# SIX_OUTPORT.net
KiCad netlist of a schematic drawn in Altium Designer
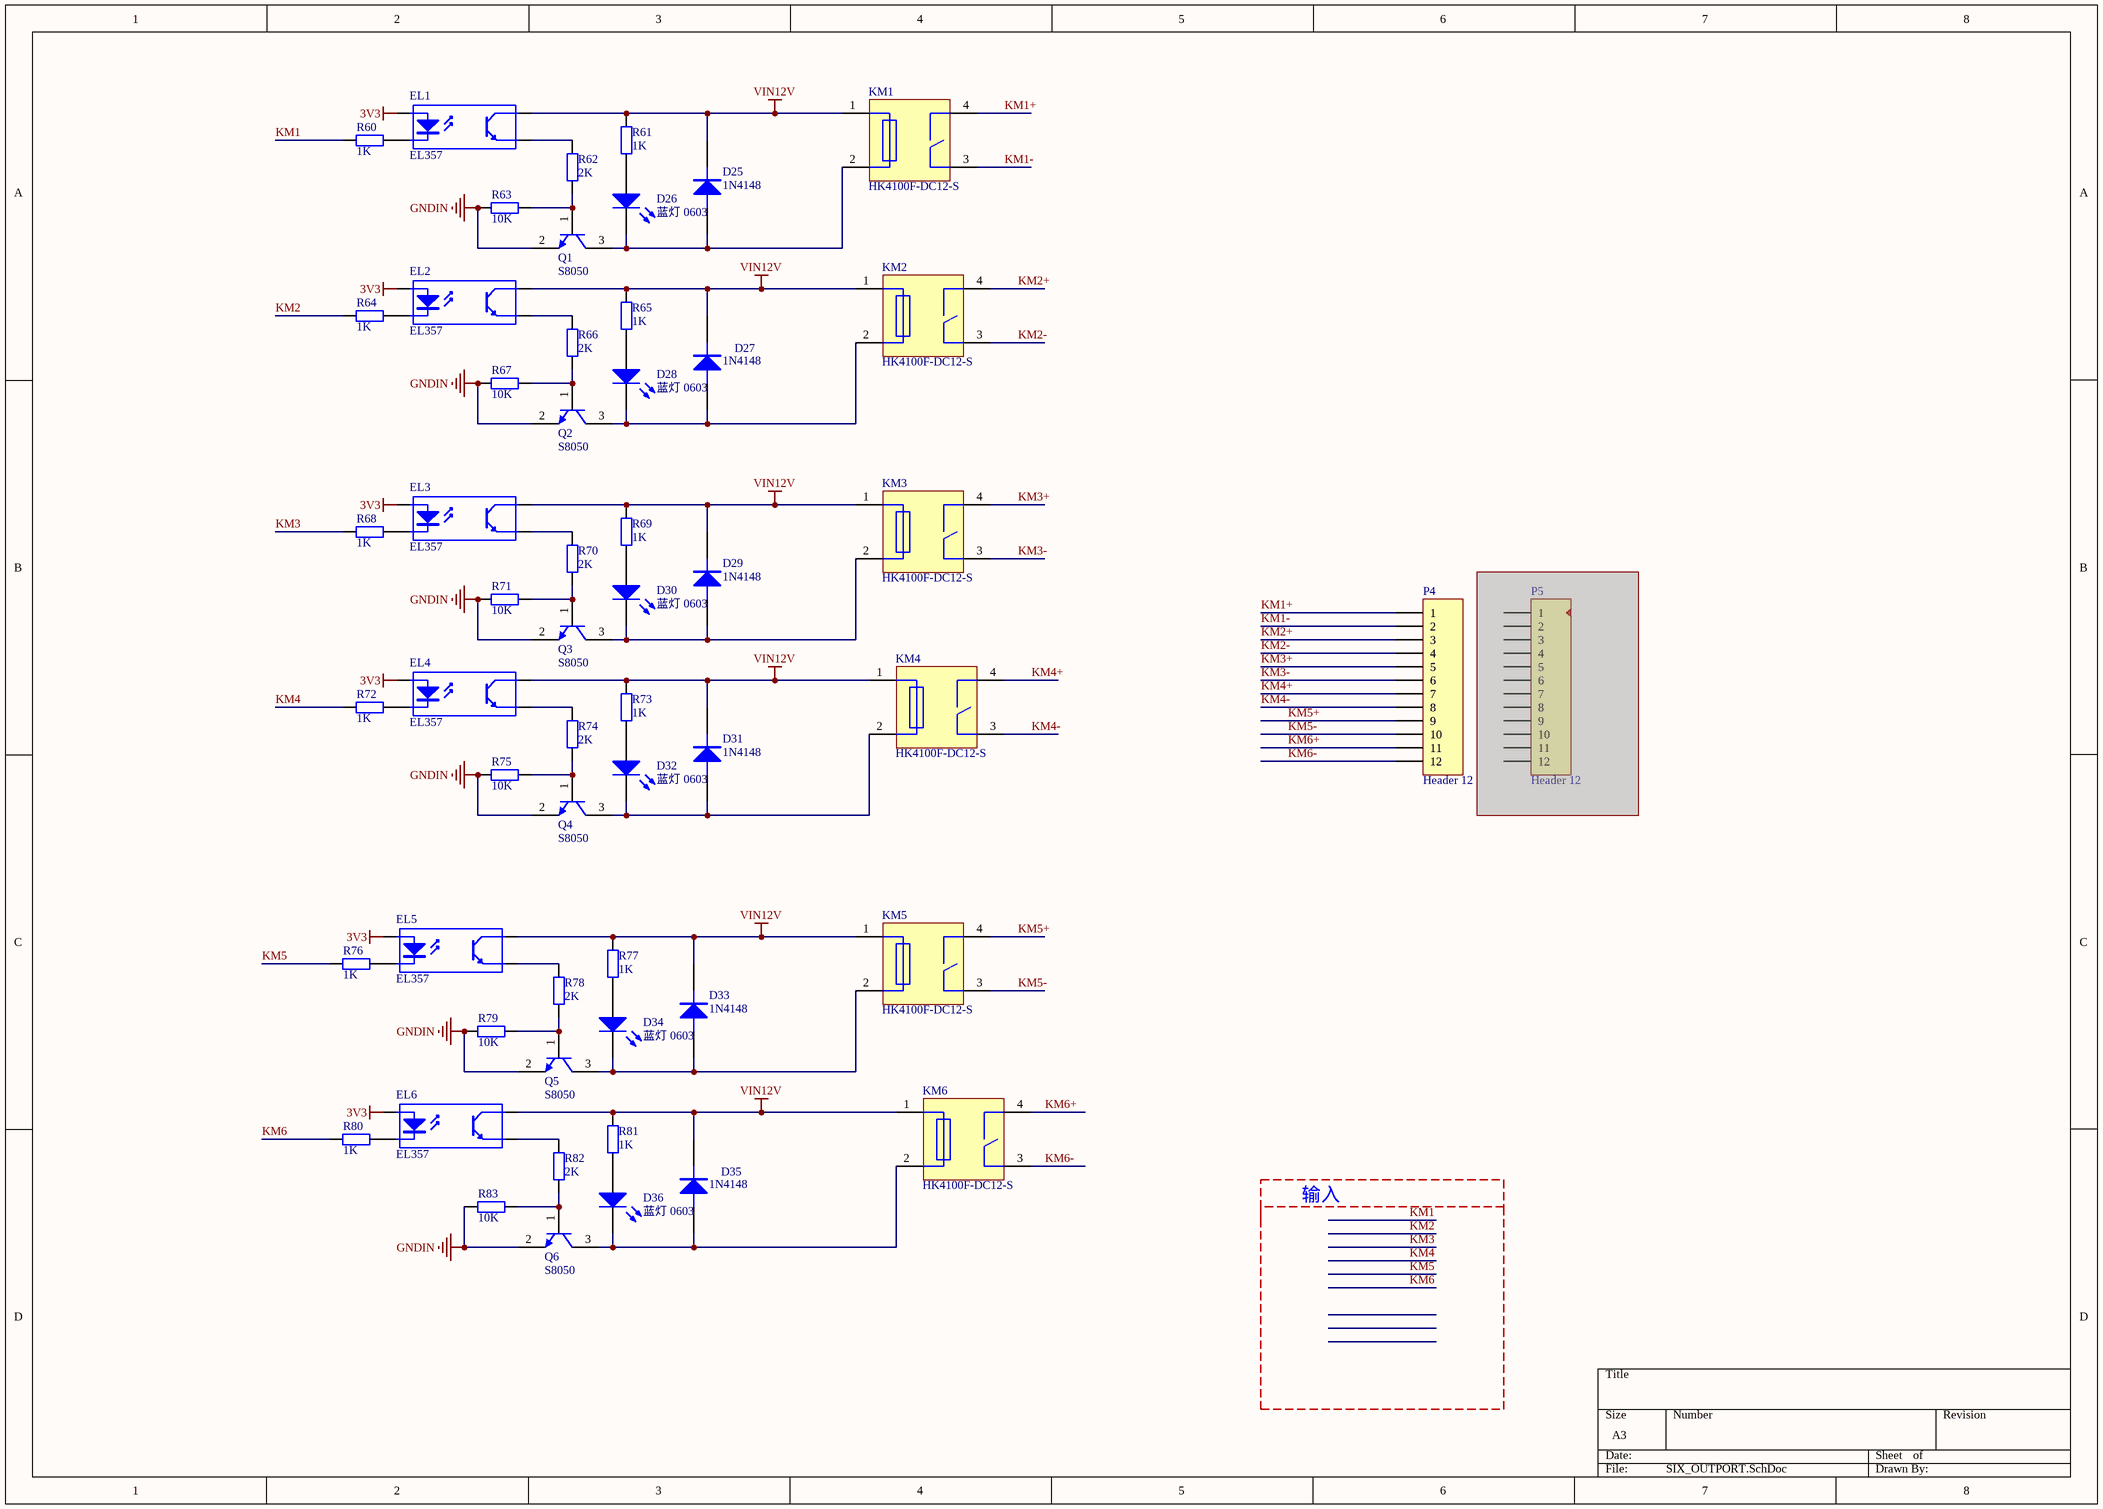
[diagram p0: SIX_OUTPORT.SchDoc]

(export (version "E")
  (design (tool "Eeschema 10.0.6"))
  (components
    (comp (ref "D25")
      (value "1N4148")
      (footprint "LC-LL-34")
      (description "Diode")
      (libsource (lib "Miscellaneous Devices") (part "DIODE"))
    )
    (comp (ref "D26")
      (value "蓝灯 0603")
      (footprint "LC-0603_LED_S1")
      (description "发光二极管")
      (libsource (lib "Miscellaneous Devices LC") (part "0603 蓝灯"))
    )
    (comp (ref "D27")
      (value "1N4148")
      (footprint "LC-LL-34")
      (description "Diode")
      (libsource (lib "Miscellaneous Devices") (part "DIODE"))
    )
    (comp (ref "D28")
      (value "蓝灯 0603")
      (footprint "LC-0603_LED_S1")
      (description "发光二极管")
      (libsource (lib "Miscellaneous Devices LC") (part "0603 蓝灯"))
    )
    (comp (ref "D29")
      (value "1N4148")
      (footprint "LC-LL-34")
      (description "Diode")
      (libsource (lib "Miscellaneous Devices") (part "DIODE"))
    )
    (comp (ref "D30")
      (value "蓝灯 0603")
      (footprint "LC-0603_LED_S1")
      (description "发光二极管")
      (libsource (lib "Miscellaneous Devices LC") (part "0603 蓝灯"))
    )
    (comp (ref "D31")
      (value "1N4148")
      (footprint "LC-LL-34")
      (description "Diode")
      (libsource (lib "Miscellaneous Devices") (part "DIODE"))
    )
    (comp (ref "D32")
      (value "蓝灯 0603")
      (footprint "LC-0603_LED_S1")
      (description "发光二极管")
      (libsource (lib "Miscellaneous Devices LC") (part "0603 蓝灯"))
    )
    (comp (ref "D33")
      (value "1N4148")
      (footprint "LC-LL-34")
      (description "Diode")
      (libsource (lib "Miscellaneous Devices") (part "DIODE"))
    )
    (comp (ref "D34")
      (value "蓝灯 0603")
      (footprint "LC-0603_LED_S1")
      (description "发光二极管")
      (libsource (lib "Miscellaneous Devices LC") (part "0603 蓝灯"))
    )
    (comp (ref "D35")
      (value "1N4148")
      (footprint "LC-LL-34")
      (description "Diode")
      (libsource (lib "Miscellaneous Devices") (part "DIODE"))
    )
    (comp (ref "D36")
      (value "蓝灯 0603")
      (footprint "LC-0603_LED_S1")
      (description "发光二极管")
      (libsource (lib "Miscellaneous Devices LC") (part "0603 蓝灯"))
    )
    (comp (ref "EL1")
      (value "EL357")
      (footprint "lc-sop-4_P2.54")
      (description "反射式光电传感器")
      (fields (field (name "PUBLISHER") "Altium Limited"))
      (libsource (lib "SCH_Footp1_Lian") (part "ST188"))
    )
    (comp (ref "EL2")
      (value "EL357")
      (footprint "lc-sop-4_P2.54")
      (description "反射式光电传感器")
      (fields (field (name "PUBLISHER") "Altium Limited"))
      (libsource (lib "SCH_Footp1_Lian") (part "ST188"))
    )
    (comp (ref "EL3")
      (value "EL357")
      (footprint "lc-sop-4_P2.54")
      (description "反射式光电传感器")
      (fields (field (name "PUBLISHER") "Altium Limited"))
      (libsource (lib "SCH_Footp1_Lian") (part "ST188"))
    )
    (comp (ref "EL4")
      (value "EL357")
      (footprint "lc-sop-4_P2.54")
      (description "反射式光电传感器")
      (fields (field (name "PUBLISHER") "Altium Limited"))
      (libsource (lib "SCH_Footp1_Lian") (part "ST188"))
    )
    (comp (ref "EL5")
      (value "EL357")
      (footprint "lc-sop-4_P2.54")
      (description "反射式光电传感器")
      (fields (field (name "PUBLISHER") "Altium Limited"))
      (libsource (lib "SCH_Footp1_Lian") (part "ST188"))
    )
    (comp (ref "EL6")
      (value "EL357")
      (footprint "lc-sop-4_P2.54")
      (description "反射式光电传感器")
      (fields (field (name "PUBLISHER") "Altium Limited"))
      (libsource (lib "SCH_Footp1_Lian") (part "ST188"))
    )
    (comp (ref "KM1")
      (value "HK4100F-DC12-S")
      (description "单刀双掷继电器")
      (libsource (lib "PCB_Project_2") (part "RELAY-HK4100F"))
    )
    (comp (ref "KM2")
      (value "HK4100F-DC12-S")
      (description "单刀双掷继电器")
      (libsource (lib "PCB_Project_2") (part "RELAY-HK4100F"))
    )
    (comp (ref "KM3")
      (value "HK4100F-DC12-S")
      (description "单刀双掷继电器")
      (libsource (lib "PCB_Project_2") (part "RELAY-HK4100F"))
    )
    (comp (ref "KM4")
      (value "HK4100F-DC12-S")
      (description "单刀双掷继电器")
      (libsource (lib "PCB_Project_2") (part "RELAY-HK4100F"))
    )
    (comp (ref "KM5")
      (value "HK4100F-DC12-S")
      (description "单刀双掷继电器")
      (libsource (lib "PCB_Project_2") (part "RELAY-HK4100F"))
    )
    (comp (ref "KM6")
      (value "HK4100F-DC12-S")
      (description "单刀双掷继电器")
      (libsource (lib "PCB_Project_2") (part "RELAY-HK4100F"))
    )
    (comp (ref "P4")
      (value "Header 12")
      (footprint "F5.08-12P")
      (description "Header, 12-Pin")
      (fields (field (name "PUBLISHER") "Altium Limited"))
      (libsource (lib "Miscellaneous Connectors") (part "Header 12"))
    )
    (comp (ref "P5")
      (value "Header 12")
      (footprint "F5.08-12P")
      (libsource (lib "HDR_fszhang") (part "Header 12"))
    )
    (comp (ref "Q1")
      (value "S8050")
      (footprint "LC-SOT-23(SOT-23-3)")
      (libsource (lib "SCH_Footp1_Lian") (part "S8050"))
    )
    (comp (ref "Q2")
      (value "S8050")
      (footprint "LC-SOT-23(SOT-23-3)")
      (libsource (lib "SCH_Footp1_Lian") (part "S8050"))
    )
    (comp (ref "Q3")
      (value "S8050")
      (footprint "LC-SOT-23(SOT-23-3)")
      (libsource (lib "SCH_Footp1_Lian") (part "S8050"))
    )
    (comp (ref "Q4")
      (value "S8050")
      (footprint "LC-SOT-23(SOT-23-3)")
      (libsource (lib "SCH_Footp1_Lian") (part "S8050"))
    )
    (comp (ref "Q5")
      (value "S8050")
      (footprint "LC-SOT-23(SOT-23-3)")
      (libsource (lib "SCH_Footp1_Lian") (part "S8050"))
    )
    (comp (ref "Q6")
      (value "S8050")
      (footprint "LC-SOT-23(SOT-23-3)")
      (libsource (lib "SCH_Footp1_Lian") (part "S8050"))
    )
    (comp (ref "R60")
      (value "1K")
      (footprint "LC-0603_R")
      (description "Resistor")
      (fields (field (name "PUBLISHER") "Altium Limited"))
      (libsource (lib "Miscellaneous Devices") (part "Res2"))
    )
    (comp (ref "R61")
      (value "1K")
      (footprint "LC-0603_R")
      (description "Resistor")
      (fields (field (name "PUBLISHER") "Altium Limited"))
      (libsource (lib "") (part "Res2_2"))
    )
    (comp (ref "R62")
      (value "2K")
      (footprint "LC-0603_R")
      (description "Resistor")
      (fields (field (name "PUBLISHER") "Altium Limited"))
      (libsource (lib "") (part "Res2_1"))
    )
    (comp (ref "R63")
      (value "10K")
      (footprint "LC-0603_R")
      (description "Resistor")
      (fields (field (name "PUBLISHER") "Altium Limited"))
      (libsource (lib "Miscellaneous Devices") (part "Res2"))
    )
    (comp (ref "R64")
      (value "1K")
      (footprint "LC-0603_R")
      (description "Resistor")
      (fields (field (name "PUBLISHER") "Altium Limited"))
      (libsource (lib "Miscellaneous Devices") (part "Res2"))
    )
    (comp (ref "R65")
      (value "1K")
      (footprint "LC-0603_R")
      (description "Resistor")
      (fields (field (name "PUBLISHER") "Altium Limited"))
      (libsource (lib "") (part "Res2_2"))
    )
    (comp (ref "R66")
      (value "2K")
      (footprint "LC-0603_R")
      (description "Resistor")
      (fields (field (name "PUBLISHER") "Altium Limited"))
      (libsource (lib "") (part "Res2_1"))
    )
    (comp (ref "R67")
      (value "10K")
      (footprint "LC-0603_R")
      (description "Resistor")
      (fields (field (name "PUBLISHER") "Altium Limited"))
      (libsource (lib "Miscellaneous Devices") (part "Res2"))
    )
    (comp (ref "R68")
      (value "1K")
      (footprint "LC-0603_R")
      (description "Resistor")
      (fields (field (name "PUBLISHER") "Altium Limited"))
      (libsource (lib "Miscellaneous Devices") (part "Res2"))
    )
    (comp (ref "R69")
      (value "1K")
      (footprint "LC-0603_R")
      (description "Resistor")
      (fields (field (name "PUBLISHER") "Altium Limited"))
      (libsource (lib "") (part "Res2_2"))
    )
    (comp (ref "R70")
      (value "2K")
      (footprint "LC-0603_R")
      (description "Resistor")
      (fields (field (name "PUBLISHER") "Altium Limited"))
      (libsource (lib "") (part "Res2_1"))
    )
    (comp (ref "R71")
      (value "10K")
      (footprint "LC-0603_R")
      (description "Resistor")
      (fields (field (name "PUBLISHER") "Altium Limited"))
      (libsource (lib "Miscellaneous Devices") (part "Res2"))
    )
    (comp (ref "R72")
      (value "1K")
      (footprint "LC-0603_R")
      (description "Resistor")
      (fields (field (name "PUBLISHER") "Altium Limited"))
      (libsource (lib "Miscellaneous Devices") (part "Res2"))
    )
    (comp (ref "R73")
      (value "1K")
      (footprint "LC-0603_R")
      (description "Resistor")
      (fields (field (name "PUBLISHER") "Altium Limited"))
      (libsource (lib "") (part "Res2_2"))
    )
    (comp (ref "R74")
      (value "2K")
      (footprint "LC-0603_R")
      (description "Resistor")
      (fields (field (name "PUBLISHER") "Altium Limited"))
      (libsource (lib "") (part "Res2_1"))
    )
    (comp (ref "R75")
      (value "10K")
      (footprint "LC-0603_R")
      (description "Resistor")
      (fields (field (name "PUBLISHER") "Altium Limited"))
      (libsource (lib "Miscellaneous Devices") (part "Res2"))
    )
    (comp (ref "R76")
      (value "1K")
      (footprint "LC-0603_R")
      (description "Resistor")
      (fields (field (name "PUBLISHER") "Altium Limited"))
      (libsource (lib "Miscellaneous Devices") (part "Res2"))
    )
    (comp (ref "R77")
      (value "1K")
      (footprint "LC-0603_R")
      (description "Resistor")
      (fields (field (name "PUBLISHER") "Altium Limited"))
      (libsource (lib "") (part "Res2_2"))
    )
    (comp (ref "R78")
      (value "2K")
      (footprint "LC-0603_R")
      (description "Resistor")
      (fields (field (name "PUBLISHER") "Altium Limited"))
      (libsource (lib "") (part "Res2_1"))
    )
    (comp (ref "R79")
      (value "10K")
      (footprint "LC-0603_R")
      (description "Resistor")
      (fields (field (name "PUBLISHER") "Altium Limited"))
      (libsource (lib "Miscellaneous Devices") (part "Res2"))
    )
    (comp (ref "R80")
      (value "1K")
      (footprint "LC-0603_R")
      (description "Resistor")
      (fields (field (name "PUBLISHER") "Altium Limited"))
      (libsource (lib "Miscellaneous Devices") (part "Res2"))
    )
    (comp (ref "R81")
      (value "1K")
      (footprint "LC-0603_R")
      (description "Resistor")
      (fields (field (name "PUBLISHER") "Altium Limited"))
      (libsource (lib "") (part "Res2_2"))
    )
    (comp (ref "R82")
      (value "2K")
      (footprint "LC-0603_R")
      (description "Resistor")
      (fields (field (name "PUBLISHER") "Altium Limited"))
      (libsource (lib "") (part "Res2_1"))
    )
    (comp (ref "R83")
      (value "10K")
      (footprint "LC-0603_R")
      (description "Resistor")
      (fields (field (name "PUBLISHER") "Altium Limited"))
      (libsource (lib "Miscellaneous Devices") (part "Res2"))
    )
  )
  (nets
    (net (code "1") (name "/KM1") (class "Default")
      (node (ref "R60") (pin "2") (pinfunction "2_2") (pintype "passive"))
    )
    (net (code "2") (name "/KM1+") (class "Default")
      (node (ref "KM1") (pin "4") (pinfunction "4_4") (pintype "passive"))
      (node (ref "P4") (pin "1") (pinfunction "1_1") (pintype "passive"))
    )
    (net (code "3") (name "/KM1-") (class "Default")
      (node (ref "KM1") (pin "3") (pinfunction "3_3") (pintype "passive"))
      (node (ref "P4") (pin "2") (pinfunction "2_2") (pintype "passive"))
    )
    (net (code "4") (name "/KM2") (class "Default")
      (node (ref "R64") (pin "2") (pinfunction "2_2") (pintype "passive"))
    )
    (net (code "5") (name "/KM2+") (class "Default")
      (node (ref "KM2") (pin "4") (pinfunction "4_4") (pintype "passive"))
      (node (ref "P4") (pin "3") (pinfunction "3_3") (pintype "passive"))
    )
    (net (code "6") (name "/KM2-") (class "Default")
      (node (ref "KM2") (pin "3") (pinfunction "3_3") (pintype "passive"))
      (node (ref "P4") (pin "4") (pinfunction "4_4") (pintype "passive"))
    )
    (net (code "7") (name "/KM3") (class "Default")
      (node (ref "R68") (pin "2") (pinfunction "2_2") (pintype "passive"))
    )
    (net (code "8") (name "/KM3+") (class "Default")
      (node (ref "KM3") (pin "4") (pinfunction "4_4") (pintype "passive"))
      (node (ref "P4") (pin "5") (pinfunction "5_5") (pintype "passive"))
    )
    (net (code "9") (name "/KM3-") (class "Default")
      (node (ref "KM3") (pin "3") (pinfunction "3_3") (pintype "passive"))
      (node (ref "P4") (pin "6") (pinfunction "6_6") (pintype "passive"))
    )
    (net (code "10") (name "/KM4") (class "Default")
      (node (ref "R72") (pin "2") (pinfunction "2_2") (pintype "passive"))
    )
    (net (code "11") (name "/KM4+") (class "Default")
      (node (ref "KM4") (pin "4") (pinfunction "4_4") (pintype "passive"))
      (node (ref "P4") (pin "7") (pinfunction "7_7") (pintype "passive"))
    )
    (net (code "12") (name "/KM4-") (class "Default")
      (node (ref "KM4") (pin "3") (pinfunction "3_3") (pintype "passive"))
      (node (ref "P4") (pin "8") (pinfunction "8_8") (pintype "passive"))
    )
    (net (code "13") (name "/KM5") (class "Default")
      (node (ref "R76") (pin "2") (pinfunction "2_2") (pintype "passive"))
    )
    (net (code "14") (name "/KM5+") (class "Default")
      (node (ref "KM5") (pin "4") (pinfunction "4_4") (pintype "passive"))
      (node (ref "P4") (pin "9") (pinfunction "9_9") (pintype "passive"))
    )
    (net (code "15") (name "/KM5-") (class "Default")
      (node (ref "KM5") (pin "3") (pinfunction "3_3") (pintype "passive"))
      (node (ref "P4") (pin "10") (pinfunction "10_10") (pintype "passive"))
    )
    (net (code "16") (name "/KM6") (class "Default")
      (node (ref "R80") (pin "2") (pinfunction "2_2") (pintype "passive"))
    )
    (net (code "17") (name "/KM6+") (class "Default")
      (node (ref "KM6") (pin "4") (pinfunction "4_4") (pintype "passive"))
      (node (ref "P4") (pin "11") (pinfunction "11_11") (pintype "passive"))
    )
    (net (code "18") (name "/KM6-") (class "Default")
      (node (ref "KM6") (pin "3") (pinfunction "3_3") (pintype "passive"))
      (node (ref "P4") (pin "12") (pinfunction "12_12") (pintype "passive"))
    )
    (net (code "19") (name "3V3") (class "Default")
      (node (ref "EL1") (pin "1") (pinfunction "A_1") (pintype "passive"))
      (node (ref "EL2") (pin "1") (pinfunction "A_1") (pintype "passive"))
      (node (ref "EL3") (pin "1") (pinfunction "A_1") (pintype "passive"))
      (node (ref "EL4") (pin "1") (pinfunction "A_1") (pintype "passive"))
      (node (ref "EL5") (pin "1") (pinfunction "A_1") (pintype "passive"))
      (node (ref "EL6") (pin "1") (pinfunction "A_1") (pintype "passive"))
    )
    (net (code "20") (name "GNDIN") (class "Default")
      (node (ref "Q1") (pin "2") (pinfunction "E_2") (pintype "passive"))
      (node (ref "Q2") (pin "2") (pinfunction "E_2") (pintype "passive"))
      (node (ref "Q3") (pin "2") (pinfunction "E_2") (pintype "passive"))
      (node (ref "Q4") (pin "2") (pinfunction "E_2") (pintype "passive"))
      (node (ref "Q5") (pin "2") (pinfunction "E_2") (pintype "passive"))
      (node (ref "Q6") (pin "2") (pinfunction "E_2") (pintype "passive"))
      (node (ref "R63") (pin "2") (pinfunction "2_2") (pintype "passive"))
      (node (ref "R67") (pin "2") (pinfunction "2_2") (pintype "passive"))
      (node (ref "R71") (pin "2") (pinfunction "2_2") (pintype "passive"))
      (node (ref "R75") (pin "2") (pinfunction "2_2") (pintype "passive"))
      (node (ref "R79") (pin "2") (pinfunction "2_2") (pintype "passive"))
      (node (ref "R83") (pin "2") (pinfunction "2_2") (pintype "passive"))
    )
    (net (code "21") (name "Net-(D25-A)") (class "Default")
      (node (ref "D25") (pin "1") (pinfunction "A_1") (pintype "passive"))
      (node (ref "D26") (pin "K") (pinfunction "K_K") (pintype "passive"))
      (node (ref "KM1") (pin "2") (pinfunction "2_2") (pintype "passive"))
      (node (ref "Q1") (pin "3") (pinfunction "C_3") (pintype "passive"))
    )
    (net (code "22") (name "Net-(D26-PadA)") (class "Default")
      (node (ref "D26") (pin "A") (pinfunction "A_A") (pintype "passive"))
      (node (ref "R61") (pin "2") (pinfunction "2_2") (pintype "passive"))
    )
    (net (code "23") (name "Net-(D27-A)") (class "Default")
      (node (ref "D27") (pin "1") (pinfunction "A_1") (pintype "passive"))
      (node (ref "D28") (pin "K") (pinfunction "K_K") (pintype "passive"))
      (node (ref "KM2") (pin "2") (pinfunction "2_2") (pintype "passive"))
      (node (ref "Q2") (pin "3") (pinfunction "C_3") (pintype "passive"))
    )
    (net (code "24") (name "Net-(D28-PadA)") (class "Default")
      (node (ref "D28") (pin "A") (pinfunction "A_A") (pintype "passive"))
      (node (ref "R65") (pin "2") (pinfunction "2_2") (pintype "passive"))
    )
    (net (code "25") (name "Net-(D29-A)") (class "Default")
      (node (ref "D29") (pin "1") (pinfunction "A_1") (pintype "passive"))
      (node (ref "D30") (pin "K") (pinfunction "K_K") (pintype "passive"))
      (node (ref "KM3") (pin "2") (pinfunction "2_2") (pintype "passive"))
      (node (ref "Q3") (pin "3") (pinfunction "C_3") (pintype "passive"))
    )
    (net (code "26") (name "Net-(D30-PadA)") (class "Default")
      (node (ref "D30") (pin "A") (pinfunction "A_A") (pintype "passive"))
      (node (ref "R69") (pin "2") (pinfunction "2_2") (pintype "passive"))
    )
    (net (code "27") (name "Net-(D31-A)") (class "Default")
      (node (ref "D31") (pin "1") (pinfunction "A_1") (pintype "passive"))
      (node (ref "D32") (pin "K") (pinfunction "K_K") (pintype "passive"))
      (node (ref "KM4") (pin "2") (pinfunction "2_2") (pintype "passive"))
      (node (ref "Q4") (pin "3") (pinfunction "C_3") (pintype "passive"))
    )
    (net (code "28") (name "Net-(D32-PadA)") (class "Default")
      (node (ref "D32") (pin "A") (pinfunction "A_A") (pintype "passive"))
      (node (ref "R73") (pin "2") (pinfunction "2_2") (pintype "passive"))
    )
    (net (code "29") (name "Net-(D33-A)") (class "Default")
      (node (ref "D33") (pin "1") (pinfunction "A_1") (pintype "passive"))
      (node (ref "D34") (pin "K") (pinfunction "K_K") (pintype "passive"))
      (node (ref "KM5") (pin "2") (pinfunction "2_2") (pintype "passive"))
      (node (ref "Q5") (pin "3") (pinfunction "C_3") (pintype "passive"))
    )
    (net (code "30") (name "Net-(D34-PadA)") (class "Default")
      (node (ref "D34") (pin "A") (pinfunction "A_A") (pintype "passive"))
      (node (ref "R77") (pin "2") (pinfunction "2_2") (pintype "passive"))
    )
    (net (code "31") (name "Net-(D35-A)") (class "Default")
      (node (ref "D35") (pin "1") (pinfunction "A_1") (pintype "passive"))
      (node (ref "D36") (pin "K") (pinfunction "K_K") (pintype "passive"))
      (node (ref "KM6") (pin "2") (pinfunction "2_2") (pintype "passive"))
      (node (ref "Q6") (pin "3") (pinfunction "C_3") (pintype "passive"))
    )
    (net (code "32") (name "Net-(D36-PadA)") (class "Default")
      (node (ref "D36") (pin "A") (pinfunction "A_A") (pintype "passive"))
      (node (ref "R81") (pin "2") (pinfunction "2_2") (pintype "passive"))
    )
    (net (code "33") (name "Net-(EL1-E)") (class "Default")
      (node (ref "EL1") (pin "3") (pinfunction "E_3") (pintype "passive"))
      (node (ref "R62") (pin "2") (pinfunction "2_2") (pintype "passive"))
    )
    (net (code "34") (name "Net-(EL1-K)") (class "Default")
      (node (ref "EL1") (pin "2") (pinfunction "K_2") (pintype "passive"))
      (node (ref "R60") (pin "1") (pinfunction "1_1") (pintype "passive"))
    )
    (net (code "35") (name "Net-(EL2-E)") (class "Default")
      (node (ref "EL2") (pin "3") (pinfunction "E_3") (pintype "passive"))
      (node (ref "R66") (pin "2") (pinfunction "2_2") (pintype "passive"))
    )
    (net (code "36") (name "Net-(EL2-K)") (class "Default")
      (node (ref "EL2") (pin "2") (pinfunction "K_2") (pintype "passive"))
      (node (ref "R64") (pin "1") (pinfunction "1_1") (pintype "passive"))
    )
    (net (code "37") (name "Net-(EL3-E)") (class "Default")
      (node (ref "EL3") (pin "3") (pinfunction "E_3") (pintype "passive"))
      (node (ref "R70") (pin "2") (pinfunction "2_2") (pintype "passive"))
    )
    (net (code "38") (name "Net-(EL3-K)") (class "Default")
      (node (ref "EL3") (pin "2") (pinfunction "K_2") (pintype "passive"))
      (node (ref "R68") (pin "1") (pinfunction "1_1") (pintype "passive"))
    )
    (net (code "39") (name "Net-(EL4-E)") (class "Default")
      (node (ref "EL4") (pin "3") (pinfunction "E_3") (pintype "passive"))
      (node (ref "R74") (pin "2") (pinfunction "2_2") (pintype "passive"))
    )
    (net (code "40") (name "Net-(EL4-K)") (class "Default")
      (node (ref "EL4") (pin "2") (pinfunction "K_2") (pintype "passive"))
      (node (ref "R72") (pin "1") (pinfunction "1_1") (pintype "passive"))
    )
    (net (code "41") (name "Net-(EL5-E)") (class "Default")
      (node (ref "EL5") (pin "3") (pinfunction "E_3") (pintype "passive"))
      (node (ref "R78") (pin "2") (pinfunction "2_2") (pintype "passive"))
    )
    (net (code "42") (name "Net-(EL5-K)") (class "Default")
      (node (ref "EL5") (pin "2") (pinfunction "K_2") (pintype "passive"))
      (node (ref "R76") (pin "1") (pinfunction "1_1") (pintype "passive"))
    )
    (net (code "43") (name "Net-(EL6-E)") (class "Default")
      (node (ref "EL6") (pin "3") (pinfunction "E_3") (pintype "passive"))
      (node (ref "R82") (pin "2") (pinfunction "2_2") (pintype "passive"))
    )
    (net (code "44") (name "Net-(EL6-K)") (class "Default")
      (node (ref "EL6") (pin "2") (pinfunction "K_2") (pintype "passive"))
      (node (ref "R80") (pin "1") (pinfunction "1_1") (pintype "passive"))
    )
    (net (code "45") (name "Net-(Q1-B)") (class "Default")
      (node (ref "Q1") (pin "1") (pinfunction "B_1") (pintype "passive"))
      (node (ref "R62") (pin "1") (pinfunction "1_1") (pintype "passive"))
      (node (ref "R63") (pin "1") (pinfunction "1_1") (pintype "passive"))
    )
    (net (code "46") (name "Net-(Q2-B)") (class "Default")
      (node (ref "Q2") (pin "1") (pinfunction "B_1") (pintype "passive"))
      (node (ref "R66") (pin "1") (pinfunction "1_1") (pintype "passive"))
      (node (ref "R67") (pin "1") (pinfunction "1_1") (pintype "passive"))
    )
    (net (code "47") (name "Net-(Q3-B)") (class "Default")
      (node (ref "Q3") (pin "1") (pinfunction "B_1") (pintype "passive"))
      (node (ref "R70") (pin "1") (pinfunction "1_1") (pintype "passive"))
      (node (ref "R71") (pin "1") (pinfunction "1_1") (pintype "passive"))
    )
    (net (code "48") (name "Net-(Q4-B)") (class "Default")
      (node (ref "Q4") (pin "1") (pinfunction "B_1") (pintype "passive"))
      (node (ref "R74") (pin "1") (pinfunction "1_1") (pintype "passive"))
      (node (ref "R75") (pin "1") (pinfunction "1_1") (pintype "passive"))
    )
    (net (code "49") (name "Net-(Q5-B)") (class "Default")
      (node (ref "Q5") (pin "1") (pinfunction "B_1") (pintype "passive"))
      (node (ref "R78") (pin "1") (pinfunction "1_1") (pintype "passive"))
      (node (ref "R79") (pin "1") (pinfunction "1_1") (pintype "passive"))
    )
    (net (code "50") (name "Net-(Q6-B)") (class "Default")
      (node (ref "Q6") (pin "1") (pinfunction "B_1") (pintype "passive"))
      (node (ref "R82") (pin "1") (pinfunction "1_1") (pintype "passive"))
      (node (ref "R83") (pin "1") (pinfunction "1_1") (pintype "passive"))
    )
    (net (code "51") (name "VIN12V") (class "Default")
      (node (ref "D25") (pin "2") (pinfunction "K_2") (pintype "passive"))
      (node (ref "D27") (pin "2") (pinfunction "K_2") (pintype "passive"))
      (node (ref "D29") (pin "2") (pinfunction "K_2") (pintype "passive"))
      (node (ref "D31") (pin "2") (pinfunction "K_2") (pintype "passive"))
      (node (ref "D33") (pin "2") (pinfunction "K_2") (pintype "passive"))
      (node (ref "D35") (pin "2") (pinfunction "K_2") (pintype "passive"))
      (node (ref "EL1") (pin "4") (pinfunction "C_4") (pintype "passive"))
      (node (ref "EL2") (pin "4") (pinfunction "C_4") (pintype "passive"))
      (node (ref "EL3") (pin "4") (pinfunction "C_4") (pintype "passive"))
      (node (ref "EL4") (pin "4") (pinfunction "C_4") (pintype "passive"))
      (node (ref "EL5") (pin "4") (pinfunction "C_4") (pintype "passive"))
      (node (ref "EL6") (pin "4") (pinfunction "C_4") (pintype "passive"))
      (node (ref "KM1") (pin "1") (pinfunction "1_1") (pintype "passive"))
      (node (ref "KM2") (pin "1") (pinfunction "1_1") (pintype "passive"))
      (node (ref "KM3") (pin "1") (pinfunction "1_1") (pintype "passive"))
      (node (ref "KM4") (pin "1") (pinfunction "1_1") (pintype "passive"))
      (node (ref "KM5") (pin "1") (pinfunction "1_1") (pintype "passive"))
      (node (ref "KM6") (pin "1") (pinfunction "1_1") (pintype "passive"))
      (node (ref "R61") (pin "1") (pinfunction "1_1") (pintype "passive"))
      (node (ref "R65") (pin "1") (pinfunction "1_1") (pintype "passive"))
      (node (ref "R69") (pin "1") (pinfunction "1_1") (pintype "passive"))
      (node (ref "R73") (pin "1") (pinfunction "1_1") (pintype "passive"))
      (node (ref "R77") (pin "1") (pinfunction "1_1") (pintype "passive"))
      (node (ref "R81") (pin "1") (pinfunction "1_1") (pintype "passive"))
    )
    (net (code "52") (name "unconnected-(P5-9-Pad8)") (class "Default")
      (node (ref "P5") (pin "8") (pinfunction "9_8") (pintype "passive"))
    )
    (net (code "53") (name "unconnected-(P5-10-Pad8)") (class "Default")
      (node (ref "P5") (pin "8") (pinfunction "10_8") (pintype "passive"))
    )
    (net (code "54") (name "unconnected-(P5-11-Pad8)") (class "Default")
      (node (ref "P5") (pin "8") (pinfunction "11_8") (pintype "passive"))
    )
    (net (code "55") (name "unconnected-(P5-12-Pad8)") (class "Default")
      (node (ref "P5") (pin "8") (pinfunction "12_8") (pintype "passive"))
    )
    (net (code "56") (name "unconnected-(P5-Pad1)") (class "Default")
      (node (ref "P5") (pin "1") (pinfunction "1_1") (pintype "passive"))
    )
    (net (code "57") (name "unconnected-(P5-Pad2)") (class "Default")
      (node (ref "P5") (pin "2") (pinfunction "2_2") (pintype "passive"))
    )
    (net (code "58") (name "unconnected-(P5-Pad3)") (class "Default")
      (node (ref "P5") (pin "3") (pinfunction "3_3") (pintype "passive"))
    )
    (net (code "59") (name "unconnected-(P5-Pad4)") (class "Default")
      (node (ref "P5") (pin "4") (pinfunction "4_4") (pintype "passive"))
    )
    (net (code "60") (name "unconnected-(P5-Pad5)") (class "Default")
      (node (ref "P5") (pin "5") (pinfunction "5_5") (pintype "passive"))
    )
    (net (code "61") (name "unconnected-(P5-Pad6)") (class "Default")
      (node (ref "P5") (pin "6") (pinfunction "6_6") (pintype "passive"))
    )
    (net (code "62") (name "unconnected-(P5-Pad7)") (class "Default")
      (node (ref "P5") (pin "7") (pinfunction "7_7") (pintype "passive"))
    )
    (net (code "63") (name "unconnected-(P5-Pad8)") (class "Default")
      (node (ref "P5") (pin "8") (pinfunction "8_8") (pintype "passive"))
    )
  )
)
